# Processor.net
KiCad netlist of a schematic drawn in Altium Designer
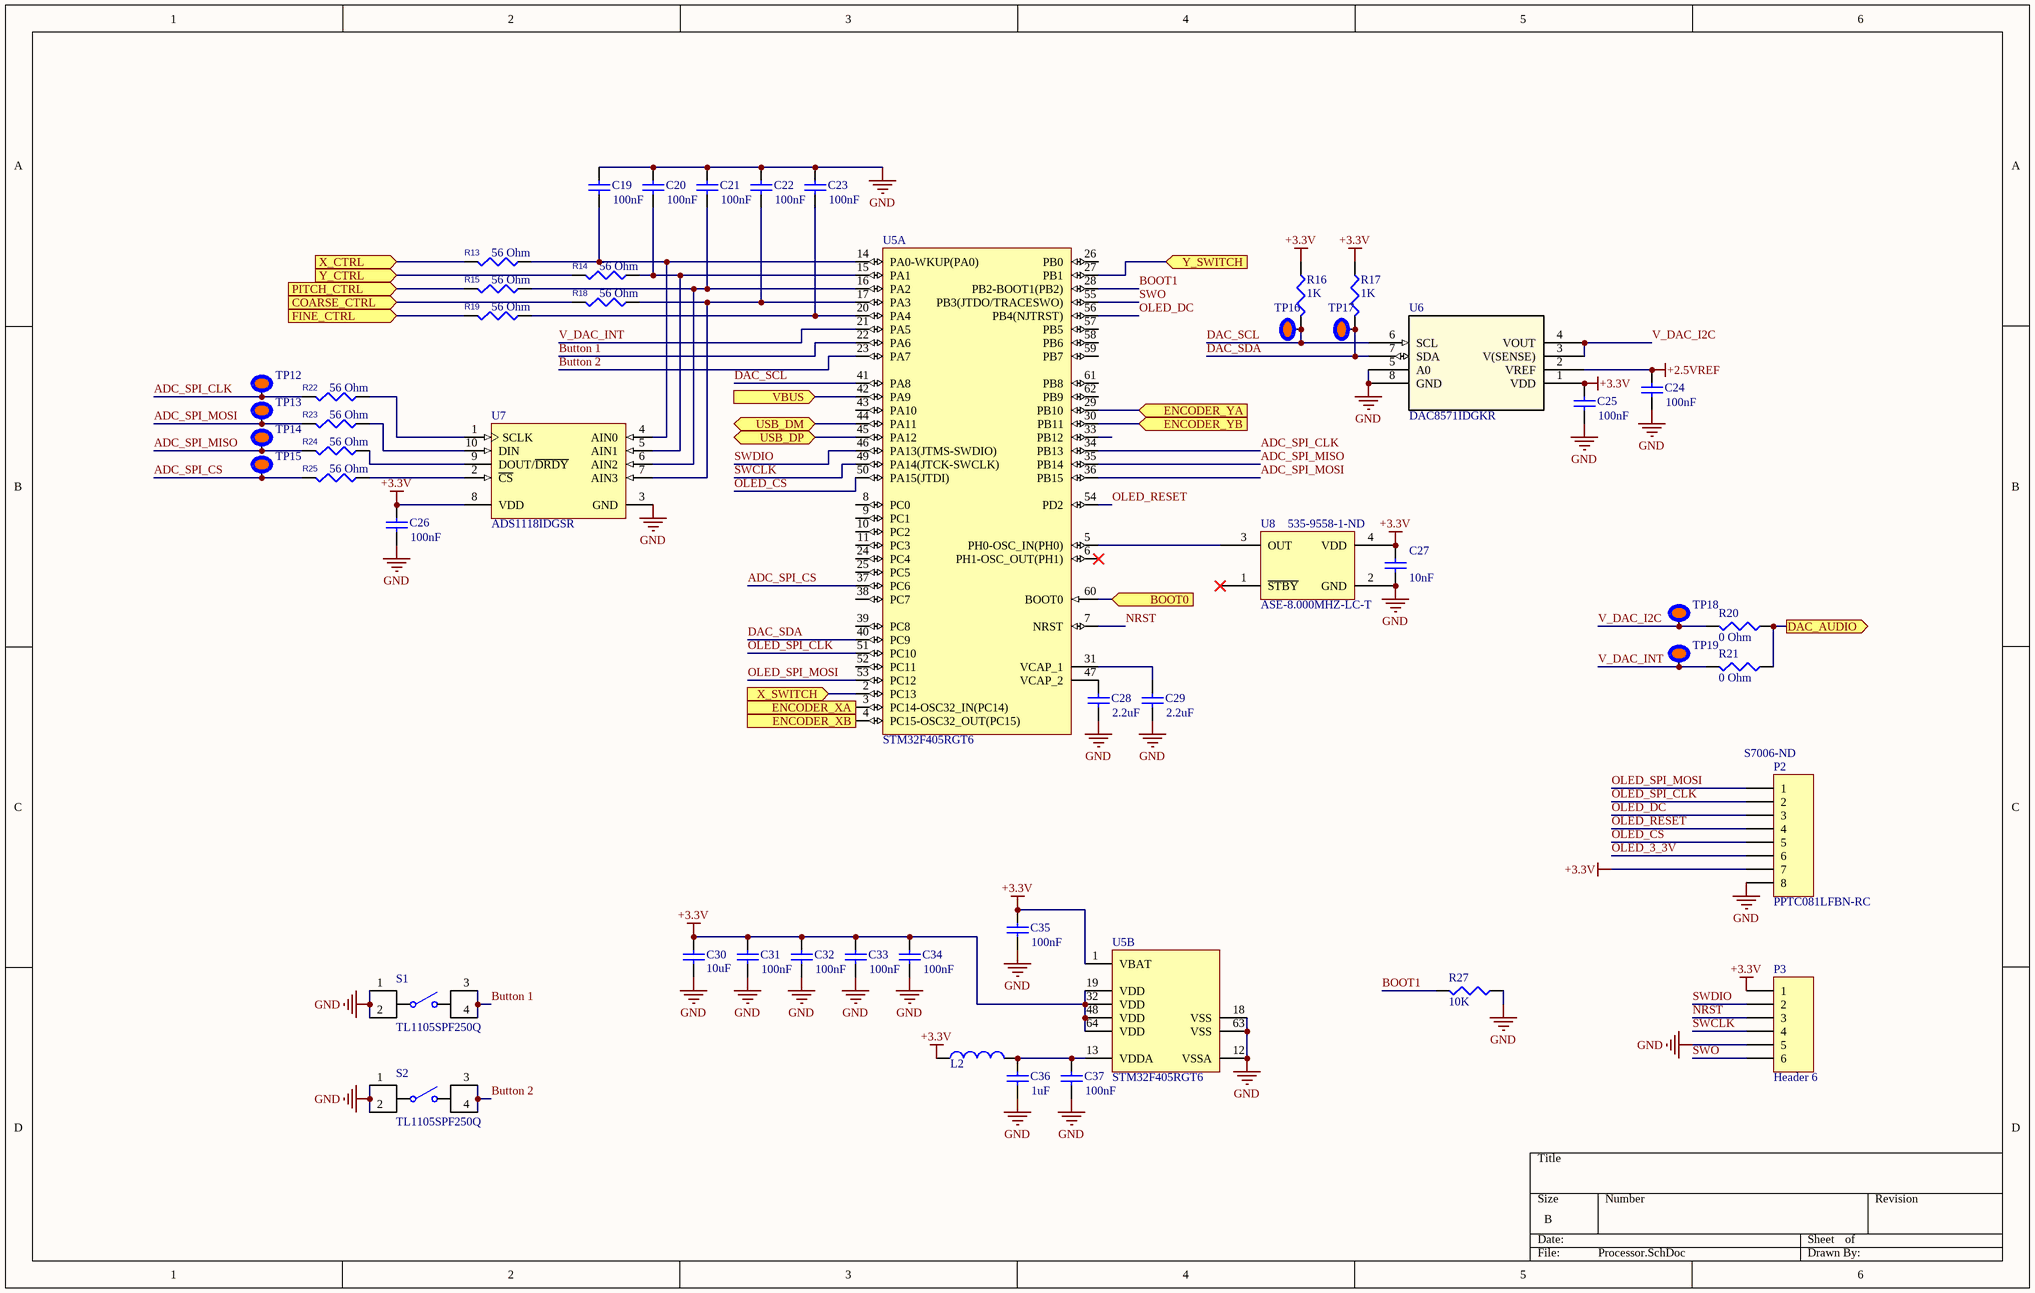
[diagram p0: Processor.SchDoc]

(export (version "E")
  (design (tool "Eeschema 10.0.6"))
  (components
    (comp (ref "C19")
      (value "100nF")
      (footprint "RES_0603")
      (description "Capacitor")
      (fields
        (field (name "MANUFACTURER") "AVX Corporation")
        (field (name "MANUFACTURER PART NUMBER") "06035G104ZAT2A")
      )
      (libsource (lib "Miscellaneous Devices") (part "Cap"))
    )
    (comp (ref "C20")
      (value "100nF")
      (footprint "RES_0603")
      (description "Capacitor")
      (fields
        (field (name "MANUFACTURER") "AVX Corporation")
        (field (name "MANUFACTURER PART NUMBER") "06035G104ZAT2A")
      )
      (libsource (lib "Miscellaneous Devices") (part "Cap"))
    )
    (comp (ref "C21")
      (value "100nF")
      (footprint "RES_0603")
      (description "Capacitor")
      (fields
        (field (name "MANUFACTURER") "AVX Corporation")
        (field (name "MANUFACTURER PART NUMBER") "06035G104ZAT2A")
      )
      (libsource (lib "Miscellaneous Devices") (part "Cap"))
    )
    (comp (ref "C22")
      (value "100nF")
      (footprint "RES_0603")
      (description "Capacitor")
      (fields
        (field (name "MANUFACTURER") "AVX Corporation")
        (field (name "MANUFACTURER PART NUMBER") "06035G104ZAT2A")
      )
      (libsource (lib "Miscellaneous Devices") (part "Cap"))
    )
    (comp (ref "C23")
      (value "100nF")
      (footprint "RES_0603")
      (description "Capacitor")
      (fields
        (field (name "MANUFACTURER") "AVX Corporation")
        (field (name "MANUFACTURER PART NUMBER") "06035G104ZAT2A")
      )
      (libsource (lib "Miscellaneous Devices") (part "Cap"))
    )
    (comp (ref "C24")
      (value "100nF")
      (footprint "RES_0603")
      (description "Capacitor")
      (fields
        (field (name "MANUFACTURER") "AVX Corporation")
        (field (name "MANUFACTURER PART NUMBER") "06035G104ZAT2A")
      )
      (libsource (lib "Miscellaneous Devices") (part "Cap"))
    )
    (comp (ref "C25")
      (value "100nF")
      (footprint "RES_0603")
      (description "Capacitor")
      (fields
        (field (name "MANUFACTURER") "AVX Corporation")
        (field (name "MANUFACTURER PART NUMBER") "06035G104ZAT2A")
      )
      (libsource (lib "Miscellaneous Devices") (part "Cap"))
    )
    (comp (ref "C26")
      (value "100nF")
      (footprint "RES_0603")
      (description "Capacitor")
      (fields
        (field (name "MANUFACTURER") "AVX Corporation")
        (field (name "MANUFACTURER PART NUMBER") "06035G104ZAT2A")
      )
      (libsource (lib "Miscellaneous Devices") (part "Cap"))
    )
    (comp (ref "C27")
      (value "10nF")
      (footprint "RES_0603")
      (description "Capacitor")
      (fields
        (field (name "MANUFACTURER") "Samsung Electro-Mechanics")
        (field (name "MANUFACTURER PART NUMBER") "CL10B103KB8NCNC")
      )
      (libsource (lib "Miscellaneous Devices") (part "Cap"))
    )
    (comp (ref "C28")
      (value "2.2uF")
      (footprint "RES_0805")
      (description "Capacitor")
      (fields
        (field (name "MANUFACTURER") "TDK")
        (field (name "MANUFACTURER PART NUMBER") "C2012JB1E225M125AC")
      )
      (libsource (lib "Miscellaneous Devices") (part "Cap"))
    )
    (comp (ref "C29")
      (value "2.2uF")
      (footprint "RES_0805")
      (description "Capacitor")
      (fields
        (field (name "MANUFACTURER") "TDK")
        (field (name "MANUFACTURER PART NUMBER") "C2012JB1E225M125AC")
      )
      (libsource (lib "Miscellaneous Devices") (part "Cap"))
    )
    (comp (ref "C30")
      (value "10uF")
      (footprint "RES_1206")
      (description "Capacitor")
      (fields
        (field (name "MANUFACTURER") "Murata")
        (field (name "MANUFACTURER PART NUMBER") "GRT31CR61H106ME01L")
      )
      (libsource (lib "Miscellaneous Devices") (part "Cap"))
    )
    (comp (ref "C31")
      (value "100nF")
      (footprint "RES_0603")
      (description "Capacitor")
      (fields
        (field (name "MANUFACTURER") "AVX Corporation")
        (field (name "MANUFACTURER PART NUMBER") "06035G104ZAT2A")
      )
      (libsource (lib "Miscellaneous Devices") (part "Cap"))
    )
    (comp (ref "C32")
      (value "100nF")
      (footprint "RES_0603")
      (description "Capacitor")
      (fields
        (field (name "MANUFACTURER") "AVX Corporation")
        (field (name "MANUFACTURER PART NUMBER") "06035G104ZAT2A")
      )
      (libsource (lib "Miscellaneous Devices") (part "Cap"))
    )
    (comp (ref "C33")
      (value "100nF")
      (footprint "RES_0603")
      (description "Capacitor")
      (fields
        (field (name "MANUFACTURER") "AVX Corporation")
        (field (name "MANUFACTURER PART NUMBER") "06035G104ZAT2A")
      )
      (libsource (lib "Miscellaneous Devices") (part "Cap"))
    )
    (comp (ref "C34")
      (value "100nF")
      (footprint "RES_0603")
      (description "Capacitor")
      (fields
        (field (name "MANUFACTURER") "AVX Corporation")
        (field (name "MANUFACTURER PART NUMBER") "06035G104ZAT2A")
      )
      (libsource (lib "Miscellaneous Devices") (part "Cap"))
    )
    (comp (ref "C35")
      (value "100nF")
      (footprint "RES_0603")
      (description "Capacitor")
      (fields
        (field (name "MANUFACTURER") "AVX Corporation")
        (field (name "MANUFACTURER PART NUMBER") "06035G104ZAT2A")
      )
      (libsource (lib "Miscellaneous Devices") (part "Cap"))
    )
    (comp (ref "C36")
      (value "1uF")
      (footprint "RES_0603")
      (description "Capacitor")
      (fields
        (field (name "MANUFACTURER") "Samsung Electro-Mechanics")
        (field (name "MANUFACTURER PART NUMBER") "CL10A105KA8NNNC")
      )
      (libsource (lib "Miscellaneous Devices") (part "Cap"))
    )
    (comp (ref "C37")
      (value "100nF")
      (footprint "RES_0603")
      (description "Capacitor")
      (fields
        (field (name "MANUFACTURER") "AVX Corporation")
        (field (name "MANUFACTURER PART NUMBER") "06035G104ZAT2A")
      )
      (libsource (lib "Miscellaneous Devices") (part "Cap"))
    )
    (comp (ref "L2")
      (value "742792651")
      (footprint "RES_0603")
      (description "Inductor")
      (fields (field (name "MANUFACTURER") "Wurth Electronics Inc."))
      (libsource (lib "Miscellaneous Devices") (part "Inductor"))
    )
    (comp (ref "P2")
      (value "PPTC081LFBN-RC")
      (footprint "HDR1X8")
      (description "Header, 8-Pin")
      (fields
        (field (name "SUPPLIER PART NUMBER 1") "S7006-ND")
        (field (name "MANUFACTURER") "Sullins Connector Solutions")
      )
      (libsource (lib "Miscellaneous Connectors") (part "MHDR1X8"))
    )
    (comp (ref "P3")
      (value "Header 6")
      (footprint "TC2030-MCP")
      (description "Header, 6-Pin")
      (fields (field (name "PUBLISHER") "Altium Limited"))
      (libsource (lib "Miscellaneous Connectors") (part "Header 6"))
    )
    (comp (ref "R13")
      (value "56 Ohm")
      (footprint "RES_0603")
      (description "Resistor")
      (fields
        (field (name "MANUFACTURER") "TE Connectivity Passive Product")
        (field (name "MANUFACTURER PART NUMBER") "CRGP0603F56R")
      )
      (libsource (lib "*") (part "R_Dup1"))
    )
    (comp (ref "R14")
      (value "56 Ohm")
      (footprint "RES_0603")
      (description "Resistor")
      (fields
        (field (name "MANUFACTURER") "TE Connectivity Passive Product")
        (field (name "MANUFACTURER PART NUMBER") "CRGP0603F56R")
      )
      (libsource (lib "*") (part "R_Dup1"))
    )
    (comp (ref "R15")
      (value "56 Ohm")
      (footprint "RES_0603")
      (description "Resistor")
      (fields
        (field (name "MANUFACTURER") "TE Connectivity Passive Product")
        (field (name "MANUFACTURER PART NUMBER") "CRGP0603F56R")
      )
      (libsource (lib "*") (part "R_Dup1"))
    )
    (comp (ref "R16")
      (value "1K")
      (footprint "RES_0603")
      (description "Resistor")
      (fields
        (field (name "MANUFACTURER") "Susumu")
        (field (name "MANUFACTURER PART NUMBER") "RR0816P-102-D")
      )
      (libsource (lib "Miscellaneous Devices") (part "Res3"))
    )
    (comp (ref "R17")
      (value "1K")
      (footprint "RES_0603")
      (description "Resistor")
      (fields
        (field (name "MANUFACTURER") "Susumu")
        (field (name "MANUFACTURER PART NUMBER") "RR0816P-102-D")
      )
      (libsource (lib "Miscellaneous Devices") (part "Res3"))
    )
    (comp (ref "R18")
      (value "56 Ohm")
      (footprint "RES_0603")
      (description "Resistor")
      (fields
        (field (name "MANUFACTURER") "TE Connectivity Passive Product")
        (field (name "MANUFACTURER PART NUMBER") "CRGP0603F56R")
      )
      (libsource (lib "*") (part "R_Dup1"))
    )
    (comp (ref "R19")
      (value "56 Ohm")
      (footprint "RES_0603")
      (description "Resistor")
      (fields
        (field (name "MANUFACTURER") "TE Connectivity Passive Product")
        (field (name "MANUFACTURER PART NUMBER") "CRGP0603F56R")
      )
      (libsource (lib "*") (part "R_Dup1"))
    )
    (comp (ref "R20")
      (value "0 Ohm")
      (footprint "RES_0603")
      (description "Resistor")
      (fields
        (field (name "MANUFACTURER") "Yageo")
        (field (name "MANUFACTURER PART NUMBER") "RC0603JR-070RL")
      )
      (libsource (lib "Miscellaneous Devices") (part "Res3"))
    )
    (comp (ref "R21")
      (value "0 Ohm")
      (footprint "RES_0603")
      (description "Resistor")
      (fields
        (field (name "MANUFACTURER") "Yageo")
        (field (name "MANUFACTURER PART NUMBER") "RC0603JR-070RL")
      )
      (libsource (lib "Miscellaneous Devices") (part "Res3"))
    )
    (comp (ref "R22")
      (value "56 Ohm")
      (footprint "RES_0603")
      (description "Resistor")
      (fields
        (field (name "MANUFACTURER") "TE Connectivity Passive Product")
        (field (name "MANUFACTURER PART NUMBER") "CRGP0603F56R")
      )
      (libsource (lib "*") (part "R_Dup1"))
    )
    (comp (ref "R23")
      (value "56 Ohm")
      (footprint "RES_0603")
      (description "Resistor")
      (fields
        (field (name "MANUFACTURER") "TE Connectivity Passive Product")
        (field (name "MANUFACTURER PART NUMBER") "CRGP0603F56R")
      )
      (libsource (lib "*") (part "R_Dup1"))
    )
    (comp (ref "R24")
      (value "56 Ohm")
      (footprint "RES_0603")
      (description "Resistor")
      (fields
        (field (name "MANUFACTURER") "TE Connectivity Passive Product")
        (field (name "MANUFACTURER PART NUMBER") "CRGP0603F56R")
      )
      (libsource (lib "*") (part "R_Dup1"))
    )
    (comp (ref "R25")
      (value "56 Ohm")
      (footprint "RES_0603")
      (description "Resistor")
      (fields
        (field (name "MANUFACTURER") "TE Connectivity Passive Product")
        (field (name "MANUFACTURER PART NUMBER") "CRGP0603F56R")
      )
      (libsource (lib "*") (part "R_Dup1"))
    )
    (comp (ref "R27")
      (value "10K")
      (footprint "RES_0805")
      (description "Resistor")
      (fields
        (field (name "MANUFACTURER") "Susumu")
        (field (name "MANUFACTURER PART NUMBER") "RR1220P-103-D")
      )
      (libsource (lib "Miscellaneous Devices") (part "Res3"))
    )
    (comp (ref "S1")
      (value "TL1105SPF250Q")
      (footprint "E_SWITCH")
      (description "SWITCH TACTILE SPST")
      (fields (field (name "MANUFACTURER") "E-Switch"))
      (libsource (lib "Custom") (part "SPST E SWITCH"))
    )
    (comp (ref "S2")
      (value "TL1105SPF250Q")
      (footprint "E_SWITCH")
      (description "SWITCH TACTILE SPST")
      (fields (field (name "MANUFACTURER") "E-Switch"))
      (libsource (lib "Custom") (part "SPST E SWITCH"))
    )
    (comp (ref "TP12")
      (value "loop test point")
      (footprint "Test Point Mt Hole")
      (description "Test Point Loop Miniature Keysone")
      (fields
        (field (name "MANUFACTURER") "Keystone Electronics")
        (field (name "MANUFACTURER PART NUMBER") "5003")
      )
      (libsource (lib "Custom") (part "Test Point"))
    )
    (comp (ref "TP13")
      (value "loop test point")
      (footprint "Test Point Mt Hole")
      (description "Test Point Loop Miniature Keysone")
      (fields
        (field (name "MANUFACTURER") "Keystone Electronics")
        (field (name "MANUFACTURER PART NUMBER") "5003")
      )
      (libsource (lib "Custom") (part "Test Point"))
    )
    (comp (ref "TP14")
      (value "loop test point")
      (footprint "Test Point Mt Hole")
      (description "Test Point Loop Miniature Keysone")
      (fields
        (field (name "MANUFACTURER") "Keystone Electronics")
        (field (name "MANUFACTURER PART NUMBER") "5003")
      )
      (libsource (lib "Custom") (part "Test Point"))
    )
    (comp (ref "TP15")
      (value "loop test point")
      (footprint "Test Point Mt Hole")
      (description "Test Point Loop Miniature Keysone")
      (fields
        (field (name "MANUFACTURER") "Keystone Electronics")
        (field (name "MANUFACTURER PART NUMBER") "5003")
      )
      (libsource (lib "Custom") (part "Test Point"))
    )
    (comp (ref "TP16")
      (value "loop test point")
      (footprint "Test Point Mt Hole")
      (description "Test Point Loop Miniature Keysone")
      (fields
        (field (name "MANUFACTURER") "Keystone Electronics")
        (field (name "MANUFACTURER PART NUMBER") "5003")
      )
      (libsource (lib "Custom") (part "Test Point"))
    )
    (comp (ref "TP17")
      (value "loop test point")
      (footprint "Test Point Mt Hole")
      (description "Test Point Loop Miniature Keysone")
      (fields
        (field (name "MANUFACTURER") "Keystone Electronics")
        (field (name "MANUFACTURER PART NUMBER") "5003")
      )
      (libsource (lib "Custom") (part "Test Point"))
    )
    (comp (ref "TP18")
      (value "loop test point")
      (footprint "Test Point Mt Hole")
      (description "Test Point Loop Miniature Keysone")
      (fields
        (field (name "MANUFACTURER") "Keystone Electronics")
        (field (name "MANUFACTURER PART NUMBER") "5003")
      )
      (libsource (lib "Custom") (part "Test Point"))
    )
    (comp (ref "TP19")
      (value "loop test point")
      (footprint "Test Point Mt Hole")
      (description "Test Point Loop Miniature Keysone")
      (fields
        (field (name "MANUFACTURER") "Keystone Electronics")
        (field (name "MANUFACTURER PART NUMBER") "5003")
      )
      (libsource (lib "Custom") (part "Test Point"))
    )
    (comp (ref "U5")
      (value "STM32F405RGT6")
      (footprint "STM-LQFP64_N")
      (fields (field (name "MANUFACTURER") "STMicroelectronics"))
      (libsource (lib "STMicroelectronics STM32 F4") (part "STM32F405RGT6"))
    )
    (comp (ref "U6")
      (value "DAC8571IDGKR")
      (footprint "DGK8")
      (fields (field (name "MANUFACTURER") "Texas Instruments"))
      (libsource (lib "Custom") (part "DAC8571IDGKR"))
    )
    (comp (ref "U7")
      (value "ADS1118IDGSR")
      (footprint "TI-DGS10_N")
      (fields (field (name "MANUFACTURER") "Texas Instruments"))
      (libsource (lib "TI Data Converters Analog to Digital Converter") (part "ADS1118IDGSR"))
    )
    (comp (ref "U8")
      (value "ASE-8.000MHZ-LC-T")
      (footprint "ASE-8.000MHZ-LC-T")
      (description "XTAL OSC XO 8.0000MHZ CMOS SMD")
      (fields
        (field (name "MANUFACTURER") "Abracon LLC")
        (field (name "SUPPLIER PART NUMBER 1") "535-9558-1-ND")
      )
      (libsource (lib "Custom") (part "ASE-8.000MHZ-LC-T"))
    )
  )
  (nets
    (net (code "1") (name "+2.5VREF") (class "Default")
      (node (ref "C24") (pin "2") (pinfunction "2_2") (pintype "passive"))
      (node (ref "U6") (pin "2") (pinfunction "VREF_2") (pintype "power_in"))
    )
    (net (code "2") (name "+3.3V") (class "Default")
      (node (ref "C25") (pin "2") (pinfunction "2_2") (pintype "passive"))
      (node (ref "C26") (pin "2") (pinfunction "2_2") (pintype "passive"))
      (node (ref "C27") (pin "2") (pinfunction "2_2") (pintype "passive"))
      (node (ref "C30") (pin "1") (pinfunction "1_1") (pintype "passive"))
      (node (ref "C31") (pin "2") (pinfunction "2_2") (pintype "passive"))
      (node (ref "C32") (pin "2") (pinfunction "2_2") (pintype "passive"))
      (node (ref "C33") (pin "2") (pinfunction "2_2") (pintype "passive"))
      (node (ref "C34") (pin "2") (pinfunction "2_2") (pintype "passive"))
      (node (ref "C35") (pin "2") (pinfunction "2_2") (pintype "passive"))
      (node (ref "L2") (pin "1") (pinfunction "1_1") (pintype "passive"))
      (node (ref "P2") (pin "7") (pinfunction "7_7") (pintype "passive"))
      (node (ref "P3") (pin "1") (pinfunction "1_1") (pintype "passive"))
      (node (ref "R16") (pin "1") (pinfunction "1_1") (pintype "passive"))
      (node (ref "R17") (pin "1") (pinfunction "1_1") (pintype "passive"))
      (node (ref "U5") (pin "1") (pinfunction "VBAT_1") (pintype "power_in"))
      (node (ref "U5") (pin "19") (pinfunction "VDD_19") (pintype "power_in"))
      (node (ref "U5") (pin "32") (pinfunction "VDD_32") (pintype "power_in"))
      (node (ref "U5") (pin "48") (pinfunction "VDD_48") (pintype "power_in"))
      (node (ref "U5") (pin "64") (pinfunction "VDD_64") (pintype "power_in"))
      (node (ref "U6") (pin "1") (pinfunction "VDD_1") (pintype "power_in"))
      (node (ref "U7") (pin "8") (pinfunction "VDD_8") (pintype "power_in"))
      (node (ref "U8") (pin "4") (pinfunction "VDD_4") (pintype "passive"))
    )
    (net (code "3") (name "/ADC_SPI_CLK") (class "Default")
      (node (ref "R22") (pin "2") (pinfunction "2_2") (pintype "passive"))
      (node (ref "TP12") (pin "1") (pinfunction "1_1") (pintype "passive"))
      (node (ref "U5") (pin "34") (pinfunction "PB13_34") (pintype "bidirectional"))
    )
    (net (code "4") (name "/ADC_SPI_CS") (class "Default")
      (node (ref "R25") (pin "2") (pinfunction "2_2") (pintype "passive"))
      (node (ref "TP15") (pin "1") (pinfunction "1_1") (pintype "passive"))
      (node (ref "U5") (pin "37") (pinfunction "PC6_37") (pintype "bidirectional"))
    )
    (net (code "5") (name "/ADC_SPI_MISO") (class "Default")
      (node (ref "R24") (pin "2") (pinfunction "2_2") (pintype "passive"))
      (node (ref "TP14") (pin "1") (pinfunction "1_1") (pintype "passive"))
      (node (ref "U5") (pin "35") (pinfunction "PB14_35") (pintype "bidirectional"))
    )
    (net (code "6") (name "/ADC_SPI_MOSI") (class "Default")
      (node (ref "R23") (pin "2") (pinfunction "2_2") (pintype "passive"))
      (node (ref "TP13") (pin "1") (pinfunction "1_1") (pintype "passive"))
      (node (ref "U5") (pin "36") (pinfunction "PB15_36") (pintype "bidirectional"))
    )
    (net (code "7") (name "/BOOT0") (class "Default")
      (node (ref "U5") (pin "60") (pinfunction "BOOT0_60") (pintype "input"))
    )
    (net (code "8") (name "/BOOT1") (class "Default")
      (node (ref "R27") (pin "2") (pinfunction "2_2") (pintype "passive"))
      (node (ref "U5") (pin "28") (pinfunction "PB2-BOOT1(PB2)_28") (pintype "bidirectional"))
    )
    (net (code "9") (name "/Button 1") (class "Default")
      (node (ref "S1") (pin "3") (pinfunction "NO_3") (pintype "passive"))
      (node (ref "S1") (pin "4") (pinfunction "NO_4") (pintype "passive"))
      (node (ref "U5") (pin "22") (pinfunction "PA6_22") (pintype "bidirectional"))
    )
    (net (code "10") (name "/Button 2") (class "Default")
      (node (ref "S2") (pin "3") (pinfunction "NO_3") (pintype "passive"))
      (node (ref "S2") (pin "4") (pinfunction "NO_4") (pintype "passive"))
      (node (ref "U5") (pin "23") (pinfunction "PA7_23") (pintype "bidirectional"))
    )
    (net (code "11") (name "/COARSE_CTRL") (class "Default")
      (node (ref "R18") (pin "2") (pinfunction "2_2") (pintype "passive"))
    )
    (net (code "12") (name "/DAC_AUDIO") (class "Default")
      (node (ref "R20") (pin "1") (pinfunction "1_1") (pintype "passive"))
      (node (ref "R21") (pin "1") (pinfunction "1_1") (pintype "passive"))
    )
    (net (code "13") (name "/DAC_SCL") (class "Default")
      (node (ref "R16") (pin "2") (pinfunction "2_2") (pintype "passive"))
      (node (ref "TP16") (pin "1") (pinfunction "1_1") (pintype "passive"))
      (node (ref "U5") (pin "41") (pinfunction "PA8_41") (pintype "bidirectional"))
      (node (ref "U6") (pin "6") (pinfunction "SCL_6") (pintype "input"))
    )
    (net (code "14") (name "/DAC_SDA") (class "Default")
      (node (ref "R17") (pin "2") (pinfunction "2_2") (pintype "passive"))
      (node (ref "TP17") (pin "1") (pinfunction "1_1") (pintype "passive"))
      (node (ref "U5") (pin "40") (pinfunction "PC9_40") (pintype "bidirectional"))
      (node (ref "U6") (pin "7") (pinfunction "SDA_7") (pintype "bidirectional"))
    )
    (net (code "15") (name "/ENCODER_XA") (class "Default")
      (node (ref "U5") (pin "3") (pinfunction "PC14-OSC32_IN(PC14)_3") (pintype "bidirectional"))
    )
    (net (code "16") (name "/ENCODER_XB") (class "Default")
      (node (ref "U5") (pin "4") (pinfunction "PC15-OSC32_OUT(PC15)_4") (pintype "bidirectional"))
    )
    (net (code "17") (name "/ENCODER_YA") (class "Default")
      (node (ref "U5") (pin "29") (pinfunction "PB10_29") (pintype "bidirectional"))
    )
    (net (code "18") (name "/ENCODER_YB") (class "Default")
      (node (ref "U5") (pin "30") (pinfunction "PB11_30") (pintype "bidirectional"))
    )
    (net (code "19") (name "/FINE_CTRL") (class "Default")
      (node (ref "R19") (pin "2") (pinfunction "2_2") (pintype "passive"))
    )
    (net (code "20") (name "/NRST") (class "Default")
      (node (ref "P3") (pin "3") (pinfunction "3_3") (pintype "passive"))
      (node (ref "U5") (pin "7") (pinfunction "NRST_7") (pintype "bidirectional"))
    )
    (net (code "21") (name "/OLED_3_3V") (class "Default")
      (node (ref "P2") (pin "6") (pinfunction "6_6") (pintype "passive"))
    )
    (net (code "22") (name "/OLED_CS") (class "Default")
      (node (ref "P2") (pin "5") (pinfunction "5_5") (pintype "passive"))
      (node (ref "U5") (pin "50") (pinfunction "PA15(JTDI)_50") (pintype "bidirectional"))
    )
    (net (code "23") (name "/OLED_DC") (class "Default")
      (node (ref "P2") (pin "3") (pinfunction "3_3") (pintype "passive"))
      (node (ref "U5") (pin "56") (pinfunction "PB4(NJTRST)_56") (pintype "bidirectional"))
    )
    (net (code "24") (name "/OLED_RESET") (class "Default")
      (node (ref "P2") (pin "4") (pinfunction "4_4") (pintype "passive"))
      (node (ref "U5") (pin "54") (pinfunction "PD2_54") (pintype "bidirectional"))
    )
    (net (code "25") (name "/OLED_SPI_CLK") (class "Default")
      (node (ref "P2") (pin "2") (pinfunction "2_2") (pintype "passive"))
      (node (ref "U5") (pin "51") (pinfunction "PC10_51") (pintype "bidirectional"))
    )
    (net (code "26") (name "/OLED_SPI_MOSI") (class "Default")
      (node (ref "P2") (pin "1") (pinfunction "1_1") (pintype "passive"))
      (node (ref "U5") (pin "53") (pinfunction "PC12_53") (pintype "bidirectional"))
    )
    (net (code "27") (name "/PITCH_CTRL") (class "Default")
      (node (ref "R15") (pin "2") (pinfunction "2_2") (pintype "passive"))
    )
    (net (code "28") (name "/SWCLK") (class "Default")
      (node (ref "P3") (pin "4") (pinfunction "4_4") (pintype "passive"))
      (node (ref "U5") (pin "49") (pinfunction "PA14(JTCK-SWCLK)_49") (pintype "bidirectional"))
    )
    (net (code "29") (name "/SWDIO") (class "Default")
      (node (ref "P3") (pin "2") (pinfunction "2_2") (pintype "passive"))
      (node (ref "U5") (pin "46") (pinfunction "PA13(JTMS-SWDIO)_46") (pintype "bidirectional"))
    )
    (net (code "30") (name "/SWO") (class "Default")
      (node (ref "P3") (pin "6") (pinfunction "6_6") (pintype "passive"))
      (node (ref "U5") (pin "55") (pinfunction "PB3(JTDO/TRACESWO)_55") (pintype "bidirectional"))
    )
    (net (code "31") (name "/USB_DM") (class "Default")
      (node (ref "U5") (pin "44") (pinfunction "PA11_44") (pintype "bidirectional"))
    )
    (net (code "32") (name "/USB_DP") (class "Default")
      (node (ref "U5") (pin "45") (pinfunction "PA12_45") (pintype "bidirectional"))
    )
    (net (code "33") (name "/VBUS") (class "Default")
      (node (ref "U5") (pin "42") (pinfunction "PA9_42") (pintype "bidirectional"))
    )
    (net (code "34") (name "/V_DAC_I2C") (class "Default")
      (node (ref "R20") (pin "2") (pinfunction "2_2") (pintype "passive"))
      (node (ref "TP18") (pin "1") (pinfunction "1_1") (pintype "passive"))
      (node (ref "U6") (pin "3") (pinfunction "V(SENSE)_3") (pintype "passive"))
      (node (ref "U6") (pin "4") (pinfunction "VOUT_4") (pintype "passive"))
    )
    (net (code "35") (name "/V_DAC_INT") (class "Default")
      (node (ref "R21") (pin "2") (pinfunction "2_2") (pintype "passive"))
      (node (ref "TP19") (pin "1") (pinfunction "1_1") (pintype "passive"))
      (node (ref "U5") (pin "21") (pinfunction "PA5_21") (pintype "bidirectional"))
    )
    (net (code "36") (name "/X_CTRL") (class "Default")
      (node (ref "R13") (pin "2") (pinfunction "2_2") (pintype "passive"))
    )
    (net (code "37") (name "/X_SWITCH") (class "Default")
      (node (ref "U5") (pin "2") (pinfunction "PC13_2") (pintype "bidirectional"))
    )
    (net (code "38") (name "/Y_CTRL") (class "Default")
      (node (ref "R14") (pin "2") (pinfunction "2_2") (pintype "passive"))
    )
    (net (code "39") (name "/Y_SWITCH") (class "Default")
      (node (ref "U5") (pin "27") (pinfunction "PB1_27") (pintype "bidirectional"))
    )
    (net (code "40") (name "GND") (class "Default")
      (node (ref "C19") (pin "2") (pinfunction "2_2") (pintype "passive"))
      (node (ref "C20") (pin "2") (pinfunction "2_2") (pintype "passive"))
      (node (ref "C21") (pin "2") (pinfunction "2_2") (pintype "passive"))
      (node (ref "C22") (pin "2") (pinfunction "2_2") (pintype "passive"))
      (node (ref "C23") (pin "2") (pinfunction "2_2") (pintype "passive"))
      (node (ref "C24") (pin "1") (pinfunction "1_1") (pintype "passive"))
      (node (ref "C25") (pin "1") (pinfunction "1_1") (pintype "passive"))
      (node (ref "C26") (pin "1") (pinfunction "1_1") (pintype "passive"))
      (node (ref "C27") (pin "1") (pinfunction "1_1") (pintype "passive"))
      (node (ref "C28") (pin "1") (pinfunction "1_1") (pintype "passive"))
      (node (ref "C29") (pin "1") (pinfunction "1_1") (pintype "passive"))
      (node (ref "C30") (pin "2") (pinfunction "2_2") (pintype "passive"))
      (node (ref "C31") (pin "1") (pinfunction "1_1") (pintype "passive"))
      (node (ref "C32") (pin "1") (pinfunction "1_1") (pintype "passive"))
      (node (ref "C33") (pin "1") (pinfunction "1_1") (pintype "passive"))
      (node (ref "C34") (pin "1") (pinfunction "1_1") (pintype "passive"))
      (node (ref "C35") (pin "1") (pinfunction "1_1") (pintype "passive"))
      (node (ref "C36") (pin "1") (pinfunction "1_1") (pintype "passive"))
      (node (ref "C37") (pin "1") (pinfunction "1_1") (pintype "passive"))
      (node (ref "P2") (pin "8") (pinfunction "8_8") (pintype "passive"))
      (node (ref "P3") (pin "5") (pinfunction "5_5") (pintype "passive"))
      (node (ref "R27") (pin "1") (pinfunction "1_1") (pintype "passive"))
      (node (ref "S1") (pin "1") (pinfunction "COMMON_1") (pintype "passive"))
      (node (ref "S1") (pin "2") (pinfunction "COMMON_2") (pintype "passive"))
      (node (ref "S2") (pin "1") (pinfunction "COMMON_1") (pintype "passive"))
      (node (ref "S2") (pin "2") (pinfunction "COMMON_2") (pintype "passive"))
      (node (ref "U5") (pin "12") (pinfunction "VSSA_12") (pintype "power_in"))
      (node (ref "U5") (pin "18") (pinfunction "VSS_18") (pintype "power_in"))
      (node (ref "U5") (pin "63") (pinfunction "VSS_63") (pintype "power_in"))
      (node (ref "U6") (pin "5") (pinfunction "A0_5") (pintype "passive"))
      (node (ref "U6") (pin "8") (pinfunction "GND_8") (pintype "power_in"))
      (node (ref "U7") (pin "3") (pinfunction "GND_3") (pintype "power_in"))
      (node (ref "U8") (pin "2") (pinfunction "GND_2") (pintype "passive"))
    )
    (net (code "41") (name "Net-(U5A-PA0-WKUP(PA0))") (class "Default")
      (node (ref "C19") (pin "1") (pinfunction "1_1") (pintype "passive"))
      (node (ref "R13") (pin "1") (pinfunction "1_1") (pintype "passive"))
      (node (ref "U5") (pin "14") (pinfunction "PA0-WKUP(PA0)_14") (pintype "bidirectional"))
      (node (ref "U7") (pin "4") (pinfunction "AIN0_4") (pintype "input"))
    )
    (net (code "42") (name "Net-(U5A-PA1)") (class "Default")
      (node (ref "C20") (pin "1") (pinfunction "1_1") (pintype "passive"))
      (node (ref "R14") (pin "1") (pinfunction "1_1") (pintype "passive"))
      (node (ref "U5") (pin "15") (pinfunction "PA1_15") (pintype "bidirectional"))
      (node (ref "U7") (pin "5") (pinfunction "AIN1_5") (pintype "input"))
    )
    (net (code "43") (name "Net-(U5A-PA2)") (class "Default")
      (node (ref "C21") (pin "1") (pinfunction "1_1") (pintype "passive"))
      (node (ref "R15") (pin "1") (pinfunction "1_1") (pintype "passive"))
      (node (ref "U5") (pin "16") (pinfunction "PA2_16") (pintype "bidirectional"))
      (node (ref "U7") (pin "6") (pinfunction "AIN2_6") (pintype "input"))
    )
    (net (code "44") (name "Net-(U5A-PA3)") (class "Default")
      (node (ref "C22") (pin "1") (pinfunction "1_1") (pintype "passive"))
      (node (ref "R18") (pin "1") (pinfunction "1_1") (pintype "passive"))
      (node (ref "U5") (pin "17") (pinfunction "PA3_17") (pintype "bidirectional"))
      (node (ref "U7") (pin "7") (pinfunction "AIN3_7") (pintype "input"))
    )
    (net (code "45") (name "Net-(U5A-PA4)") (class "Default")
      (node (ref "C23") (pin "1") (pinfunction "1_1") (pintype "passive"))
      (node (ref "R19") (pin "1") (pinfunction "1_1") (pintype "passive"))
      (node (ref "U5") (pin "20") (pinfunction "PA4_20") (pintype "bidirectional"))
    )
    (net (code "46") (name "Net-(U5A-PH0-OSC_IN(PH0))") (class "Default")
      (node (ref "U5") (pin "5") (pinfunction "PH0-OSC_IN(PH0)_5") (pintype "bidirectional"))
      (node (ref "U8") (pin "3") (pinfunction "OUT_3") (pintype "passive"))
    )
    (net (code "47") (name "Net-(U5A-VCAP_1)") (class "Default")
      (node (ref "C29") (pin "2") (pinfunction "2_2") (pintype "passive"))
      (node (ref "U5") (pin "31") (pinfunction "VCAP_1_31") (pintype "power_in"))
    )
    (net (code "48") (name "Net-(U5A-VCAP_2)") (class "Default")
      (node (ref "C28") (pin "2") (pinfunction "2_2") (pintype "passive"))
      (node (ref "U5") (pin "47") (pinfunction "VCAP_2_47") (pintype "power_in"))
    )
    (net (code "49") (name "Net-(U5B-VDDA)") (class "Default")
      (node (ref "C36") (pin "2") (pinfunction "2_2") (pintype "passive"))
      (node (ref "C37") (pin "2") (pinfunction "2_2") (pintype "passive"))
      (node (ref "L2") (pin "2") (pinfunction "2_2") (pintype "passive"))
      (node (ref "U5") (pin "13") (pinfunction "VDDA_13") (pintype "power_in"))
    )
    (net (code "50") (name "Net-(U7-DIN)") (class "Default")
      (node (ref "R23") (pin "1") (pinfunction "1_1") (pintype "passive"))
      (node (ref "U7") (pin "10") (pinfunction "DIN_10") (pintype "input"))
    )
    (net (code "51") (name "Net-(U7-DOUT{slash}~{DRDY})") (class "Default")
      (node (ref "R24") (pin "1") (pinfunction "1_1") (pintype "passive"))
      (node (ref "U7") (pin "9") (pinfunction "DOUT/~{DRDY}_9") (pintype "tri_state"))
    )
    (net (code "52") (name "Net-(U7-SCLK)") (class "Default")
      (node (ref "R22") (pin "1") (pinfunction "1_1") (pintype "passive"))
      (node (ref "U7") (pin "1") (pinfunction "SCLK_1") (pintype "input"))
    )
    (net (code "53") (name "Net-(U7-~{CS})") (class "Default")
      (node (ref "R25") (pin "1") (pinfunction "1_1") (pintype "passive"))
      (node (ref "U7") (pin "2") (pinfunction "~{CS}_2") (pintype "input"))
    )
    (net (code "54") (name "unconnected-(U5A-PA10-Pad43)") (class "Default")
      (node (ref "U5") (pin "43") (pinfunction "PA10_43") (pintype "bidirectional"))
    )
    (net (code "55") (name "unconnected-(U5A-PB0-Pad26)") (class "Default")
      (node (ref "U5") (pin "26") (pinfunction "PB0_26") (pintype "bidirectional"))
    )
    (net (code "56") (name "unconnected-(U5A-PB5-Pad57)") (class "Default")
      (node (ref "U5") (pin "57") (pinfunction "PB5_57") (pintype "bidirectional"))
    )
    (net (code "57") (name "unconnected-(U5A-PB6-Pad58)") (class "Default")
      (node (ref "U5") (pin "58") (pinfunction "PB6_58") (pintype "bidirectional"))
    )
    (net (code "58") (name "unconnected-(U5A-PB7-Pad59)") (class "Default")
      (node (ref "U5") (pin "59") (pinfunction "PB7_59") (pintype "bidirectional"))
    )
    (net (code "59") (name "unconnected-(U5A-PB8-Pad61)") (class "Default")
      (node (ref "U5") (pin "61") (pinfunction "PB8_61") (pintype "bidirectional"))
    )
    (net (code "60") (name "unconnected-(U5A-PB9-Pad62)") (class "Default")
      (node (ref "U5") (pin "62") (pinfunction "PB9_62") (pintype "bidirectional"))
    )
    (net (code "61") (name "unconnected-(U5A-PB12-Pad33)") (class "Default")
      (node (ref "U5") (pin "33") (pinfunction "PB12_33") (pintype "bidirectional"))
    )
    (net (code "62") (name "unconnected-(U5A-PC0-Pad8)") (class "Default")
      (node (ref "U5") (pin "8") (pinfunction "PC0_8") (pintype "bidirectional"))
    )
    (net (code "63") (name "unconnected-(U5A-PC1-Pad9)") (class "Default")
      (node (ref "U5") (pin "9") (pinfunction "PC1_9") (pintype "bidirectional"))
    )
    (net (code "64") (name "unconnected-(U5A-PC2-Pad10)") (class "Default")
      (node (ref "U5") (pin "10") (pinfunction "PC2_10") (pintype "bidirectional"))
    )
    (net (code "65") (name "unconnected-(U5A-PC3-Pad11)") (class "Default")
      (node (ref "U5") (pin "11") (pinfunction "PC3_11") (pintype "bidirectional"))
    )
    (net (code "66") (name "unconnected-(U5A-PC4-Pad24)") (class "Default")
      (node (ref "U5") (pin "24") (pinfunction "PC4_24") (pintype "bidirectional"))
    )
    (net (code "67") (name "unconnected-(U5A-PC5-Pad25)") (class "Default")
      (node (ref "U5") (pin "25") (pinfunction "PC5_25") (pintype "bidirectional"))
    )
    (net (code "68") (name "unconnected-(U5A-PC7-Pad38)") (class "Default")
      (node (ref "U5") (pin "38") (pinfunction "PC7_38") (pintype "bidirectional"))
    )
    (net (code "69") (name "unconnected-(U5A-PC8-Pad39)") (class "Default")
      (node (ref "U5") (pin "39") (pinfunction "PC8_39") (pintype "bidirectional"))
    )
    (net (code "70") (name "unconnected-(U5A-PC11-Pad52)") (class "Default")
      (node (ref "U5") (pin "52") (pinfunction "PC11_52") (pintype "bidirectional"))
    )
    (net (code "71") (name "unconnected-(U5A-PH1-OSC_OUT(PH1)-Pad6)") (class "Default")
      (node (ref "U5") (pin "6") (pinfunction "PH1-OSC_OUT(PH1)_6") (pintype "bidirectional+no_connect"))
    )
    (net (code "72") (name "unconnected-(U8-~{STBY}-Pad1)") (class "Default")
      (node (ref "U8") (pin "1") (pinfunction "~{STBY}_1") (pintype "passive+no_connect"))
    )
  )
)
